# bk-circ4-S.net
KiCad netlist of a schematic drawn in EAGLE
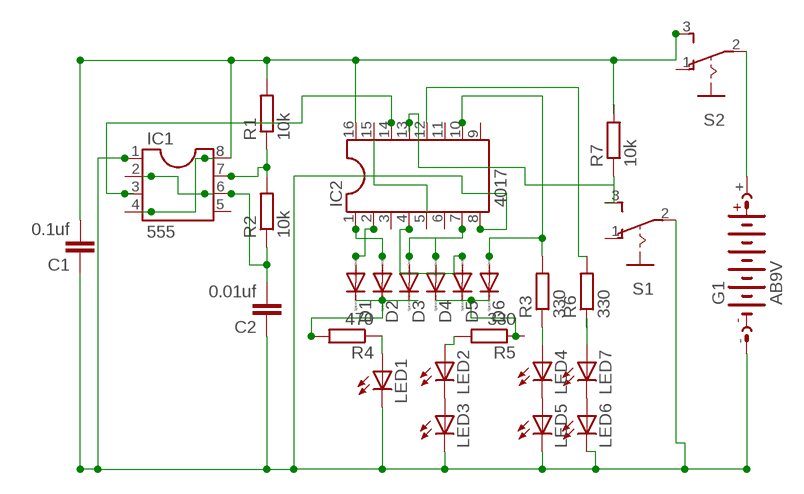
[diagram p0: schematic, sheet 1]

(export (version "E")
  (design (tool "Eeschema 10.0.6"))
  (components
    (comp (ref "C1")
      (value "0.1uf")
      (footprint "eagle-import:C025-024X044")
      (libsource (lib "eagle-import") (part "C-EU025-024X044"))
    )
    (comp (ref "C2")
      (value "0.01uf")
      (footprint "eagle-import:C025-024X044")
      (libsource (lib "eagle-import") (part "C-EU025-024X044"))
    )
    (comp (ref "D1")
      (value "1N4004")
      (footprint "eagle-import:DO41-10")
      (libsource (lib "eagle-import") (part "1N4004"))
    )
    (comp (ref "D2")
      (value "1N4004")
      (footprint "eagle-import:DO41-10")
      (libsource (lib "eagle-import") (part "1N4004"))
    )
    (comp (ref "D3")
      (value "1N4004")
      (footprint "eagle-import:DO41-10")
      (libsource (lib "eagle-import") (part "1N4004"))
    )
    (comp (ref "D4")
      (value "1N4004")
      (footprint "eagle-import:DO41-10")
      (libsource (lib "eagle-import") (part "1N4004"))
    )
    (comp (ref "D5")
      (value "1N4004")
      (footprint "eagle-import:DO41-10")
      (libsource (lib "eagle-import") (part "1N4004"))
    )
    (comp (ref "D6")
      (value "1N4004")
      (footprint "eagle-import:DO41-10")
      (libsource (lib "eagle-import") (part "1N4004"))
    )
    (comp (ref "G1")
      (value "AB9V")
      (footprint "eagle-import:AB9V")
      (libsource (lib "eagle-import") (part "AB9V"))
    )
    (comp (ref "IC1")
      (value "555")
      (footprint "eagle-import:DIL08")
      (libsource (lib "eagle-import") (part "DIL8"))
    )
    (comp (ref "IC2")
      (value "4017")
      (footprint "eagle-import:DIL16")
      (libsource (lib "eagle-import") (part "DIL16"))
    )
    (comp (ref "LED1")
      (value "LED3MM")
      (footprint "eagle-import:LED3MM")
      (libsource (lib "eagle-import") (part "LED3MM"))
    )
    (comp (ref "LED2")
      (value "LED3MM")
      (footprint "eagle-import:LED3MM")
      (libsource (lib "eagle-import") (part "LED3MM"))
    )
    (comp (ref "LED3")
      (value "LED3MM")
      (footprint "eagle-import:LED3MM")
      (libsource (lib "eagle-import") (part "LED3MM"))
    )
    (comp (ref "LED4")
      (value "LED3MM")
      (footprint "eagle-import:LED3MM")
      (libsource (lib "eagle-import") (part "LED3MM"))
    )
    (comp (ref "LED5")
      (value "LED3MM")
      (footprint "eagle-import:LED3MM")
      (libsource (lib "eagle-import") (part "LED3MM"))
    )
    (comp (ref "LED6")
      (value "LED3MM")
      (footprint "eagle-import:LED3MM")
      (libsource (lib "eagle-import") (part "LED3MM"))
    )
    (comp (ref "LED7")
      (value "LED3MM")
      (footprint "eagle-import:LED3MM")
      (libsource (lib "eagle-import") (part "LED3MM"))
    )
    (comp (ref "R1")
      (value "10k")
      (footprint "eagle-import:0207_7")
      (libsource (lib "eagle-import") (part "R-EU_0207/7"))
    )
    (comp (ref "R2")
      (value "10k")
      (footprint "eagle-import:0207_7")
      (libsource (lib "eagle-import") (part "R-EU_0207/7"))
    )
    (comp (ref "R3")
      (value "330")
      (footprint "eagle-import:0207_7")
      (libsource (lib "eagle-import") (part "R-EU_0207/7"))
    )
    (comp (ref "R4")
      (value "470")
      (footprint "eagle-import:0207_7")
      (libsource (lib "eagle-import") (part "R-EU_0207/7"))
    )
    (comp (ref "R5")
      (value "330")
      (footprint "eagle-import:0207_7")
      (libsource (lib "eagle-import") (part "R-EU_0207/7"))
    )
    (comp (ref "R6")
      (value "330")
      (footprint "eagle-import:0207_7")
      (libsource (lib "eagle-import") (part "R-EU_0207/7"))
    )
    (comp (ref "R7")
      (value "10k")
      (footprint "eagle-import:0207_7")
      (libsource (lib "eagle-import") (part "R-EU_0207/7"))
    )
    (comp (ref "S1")
      (value "255SB")
      (footprint "eagle-import:255SB")
      (libsource (lib "eagle-import") (part "255SB"))
    )
    (comp (ref "S2")
      (value "255SB")
      (footprint "eagle-import:255SB")
      (libsource (lib "eagle-import") (part "255SB"))
    )
  )
  (nets
    (net (code "1") (name "Net-(C2-Pad2)") (class "Default")
      (node (ref "C2") (pin "2") (pinfunction "2_2") (pintype "passive"))
      (node (ref "IC1") (pin "6") (pinfunction "6_6") (pintype "passive"))
      (node (ref "R2") (pin "1") (pinfunction "1_1") (pintype "passive"))
    )
    (net (code "2") (name "Net-(D1-PadC)") (class "Default")
      (node (ref "D1") (pin "C") (pinfunction "C_C") (pintype "passive"))
      (node (ref "D2") (pin "C") (pinfunction "C_C") (pintype "passive"))
      (node (ref "R4") (pin "2") (pinfunction "2_2") (pintype "passive"))
    )
    (net (code "3") (name "Net-(D4-PadC)") (class "Default")
      (node (ref "D4") (pin "C") (pinfunction "C_C") (pintype "passive"))
      (node (ref "D6") (pin "C") (pinfunction "C_C") (pintype "passive"))
    )
    (net (code "4") (name "Net-(IC1-Pad3)") (class "Default")
      (node (ref "IC1") (pin "3") (pinfunction "3_3") (pintype "passive"))
      (node (ref "IC2") (pin "14") (pinfunction "14_14") (pintype "passive"))
    )
    (net (code "5") (name "Net-(IC1-Pad7)") (class "Default")
      (node (ref "IC1") (pin "7") (pinfunction "7_7") (pintype "passive"))
      (node (ref "R1") (pin "1") (pinfunction "1_1") (pintype "passive"))
      (node (ref "R2") (pin "2") (pinfunction "2_2") (pintype "passive"))
    )
    (net (code "6") (name "Net-(IC2-Pad10)") (class "Default")
      (node (ref "IC2") (pin "10") (pinfunction "10_10") (pintype "passive"))
      (node (ref "R3") (pin "2") (pinfunction "2_2") (pintype "passive"))
    )
    (net (code "7") (name "Net-(IC2-Pad12)") (class "Default")
      (node (ref "IC2") (pin "12") (pinfunction "12_12") (pintype "passive"))
      (node (ref "R6") (pin "2") (pinfunction "2_2") (pintype "passive"))
    )
    (net (code "8") (name "Net-(LED1-C)") (class "Default")
      (node (ref "C1") (pin "1") (pinfunction "1_1") (pintype "passive"))
      (node (ref "C2") (pin "1") (pinfunction "1_1") (pintype "passive"))
      (node (ref "G1") (pin "-") (pinfunction "-_-") (pintype "passive"))
      (node (ref "IC1") (pin "1") (pinfunction "1_1") (pintype "passive"))
      (node (ref "IC2") (pin "8") (pinfunction "8_8") (pintype "passive"))
      (node (ref "LED1") (pin "K") (pinfunction "C_K") (pintype "passive"))
      (node (ref "LED3") (pin "K") (pinfunction "C_K") (pintype "passive"))
      (node (ref "LED5") (pin "K") (pinfunction "C_K") (pintype "passive"))
      (node (ref "LED6") (pin "K") (pinfunction "C_K") (pintype "passive"))
      (node (ref "S1") (pin "2") (pinfunction "P_2") (pintype "passive"))
    )
    (net (code "9") (name "Net-(LED1-PadA)") (class "Default")
      (node (ref "LED1") (pin "A") (pinfunction "A_A") (pintype "passive"))
      (node (ref "R4") (pin "1") (pinfunction "1_1") (pintype "passive"))
    )
    (net (code "10") (name "Net-(LED2-C)") (class "Default")
      (node (ref "LED2") (pin "K") (pinfunction "C_K") (pintype "passive"))
      (node (ref "LED3") (pin "A") (pinfunction "A_A") (pintype "passive"))
    )
    (net (code "11") (name "Net-(LED2-PadA)") (class "Default")
      (node (ref "LED2") (pin "A") (pinfunction "A_A") (pintype "passive"))
      (node (ref "R5") (pin "2") (pinfunction "2_2") (pintype "passive"))
    )
    (net (code "12") (name "Net-(LED4-C)") (class "Default")
      (node (ref "LED4") (pin "K") (pinfunction "C_K") (pintype "passive"))
      (node (ref "LED5") (pin "A") (pinfunction "A_A") (pintype "passive"))
    )
    (net (code "13") (name "Net-(LED4-PadA)") (class "Default")
      (node (ref "LED4") (pin "A") (pinfunction "A_A") (pintype "passive"))
      (node (ref "R3") (pin "1") (pinfunction "1_1") (pintype "passive"))
    )
    (net (code "14") (name "Net-(LED7-C)") (class "Default")
      (node (ref "LED6") (pin "A") (pinfunction "A_A") (pintype "passive"))
      (node (ref "LED7") (pin "K") (pinfunction "C_K") (pintype "passive"))
    )
    (net (code "15") (name "Net-(S1-S)") (class "Default")
      (node (ref "IC2") (pin "13") (pinfunction "13_13") (pintype "passive"))
      (node (ref "R7") (pin "1") (pinfunction "1_1") (pintype "passive"))
      (node (ref "S1") (pin "3") (pinfunction "S_3") (pintype "passive"))
    )
    (net (code "16") (name "Net-(S2-P)") (class "Default")
      (node (ref "G1") (pin "+") (pinfunction "+_+") (pintype "passive"))
      (node (ref "S2") (pin "2") (pinfunction "P_2") (pintype "passive"))
    )
    (net (code "17") (name "Net-(S2-S)") (class "Default")
      (node (ref "C1") (pin "2") (pinfunction "2_2") (pintype "passive"))
      (node (ref "IC1") (pin "8") (pinfunction "8_8") (pintype "passive"))
      (node (ref "IC2") (pin "16") (pinfunction "16_16") (pintype "passive"))
      (node (ref "R1") (pin "2") (pinfunction "2_2") (pintype "passive"))
      (node (ref "S2") (pin "3") (pinfunction "S_3") (pintype "passive"))
    )
    (net (code "18") (name "unconnected-(D1-PadA)") (class "Default")
      (node (ref "D1") (pin "A") (pinfunction "A_A") (pintype "passive"))
    )
    (net (code "19") (name "unconnected-(D2-PadA)") (class "Default")
      (node (ref "D2") (pin "A") (pinfunction "A_A") (pintype "passive"))
    )
    (net (code "20") (name "unconnected-(D3-PadA)") (class "Default")
      (node (ref "D3") (pin "A") (pinfunction "A_A") (pintype "passive"))
    )
    (net (code "21") (name "unconnected-(D3-PadC)") (class "Default")
      (node (ref "D3") (pin "C") (pinfunction "C_C") (pintype "passive"))
    )
    (net (code "22") (name "unconnected-(D4-PadA)") (class "Default")
      (node (ref "D4") (pin "A") (pinfunction "A_A") (pintype "passive"))
    )
    (net (code "23") (name "unconnected-(D5-PadA)") (class "Default")
      (node (ref "D5") (pin "A") (pinfunction "A_A") (pintype "passive"))
    )
    (net (code "24") (name "unconnected-(D5-PadC)") (class "Default")
      (node (ref "D5") (pin "C") (pinfunction "C_C") (pintype "passive"))
    )
    (net (code "25") (name "unconnected-(D6-PadA)") (class "Default")
      (node (ref "D6") (pin "A") (pinfunction "A_A") (pintype "passive"))
    )
    (net (code "26") (name "unconnected-(IC1-Pad2)") (class "Default")
      (node (ref "IC1") (pin "2") (pinfunction "2_2") (pintype "passive"))
    )
    (net (code "27") (name "unconnected-(IC1-Pad4)") (class "Default")
      (node (ref "IC1") (pin "4") (pinfunction "4_4") (pintype "passive"))
    )
    (net (code "28") (name "unconnected-(IC1-Pad5)") (class "Default")
      (node (ref "IC1") (pin "5") (pinfunction "5_5") (pintype "passive"))
    )
    (net (code "29") (name "unconnected-(IC2-Pad1)") (class "Default")
      (node (ref "IC2") (pin "1") (pinfunction "1_1") (pintype "passive"))
    )
    (net (code "30") (name "unconnected-(IC2-Pad2)") (class "Default")
      (node (ref "IC2") (pin "2") (pinfunction "2_2") (pintype "passive"))
    )
    (net (code "31") (name "unconnected-(IC2-Pad3)") (class "Default")
      (node (ref "IC2") (pin "3") (pinfunction "3_3") (pintype "passive"))
    )
    (net (code "32") (name "unconnected-(IC2-Pad4)") (class "Default")
      (node (ref "IC2") (pin "4") (pinfunction "4_4") (pintype "passive"))
    )
    (net (code "33") (name "unconnected-(IC2-Pad5)") (class "Default")
      (node (ref "IC2") (pin "5") (pinfunction "5_5") (pintype "passive"))
    )
    (net (code "34") (name "unconnected-(IC2-Pad6)") (class "Default")
      (node (ref "IC2") (pin "6") (pinfunction "6_6") (pintype "passive"))
    )
    (net (code "35") (name "unconnected-(IC2-Pad7)") (class "Default")
      (node (ref "IC2") (pin "7") (pinfunction "7_7") (pintype "passive"))
    )
    (net (code "36") (name "unconnected-(IC2-Pad9)") (class "Default")
      (node (ref "IC2") (pin "9") (pinfunction "9_9") (pintype "passive"))
    )
    (net (code "37") (name "unconnected-(IC2-Pad11)") (class "Default")
      (node (ref "IC2") (pin "11") (pinfunction "11_11") (pintype "passive"))
    )
    (net (code "38") (name "unconnected-(IC2-Pad15)") (class "Default")
      (node (ref "IC2") (pin "15") (pinfunction "15_15") (pintype "passive"))
    )
    (net (code "39") (name "unconnected-(LED7-PadA)") (class "Default")
      (node (ref "LED7") (pin "A") (pinfunction "A_A") (pintype "passive"))
    )
    (net (code "40") (name "unconnected-(R5-Pad1)") (class "Default")
      (node (ref "R5") (pin "1") (pinfunction "1_1") (pintype "passive"))
    )
    (net (code "41") (name "unconnected-(R6-Pad1)") (class "Default")
      (node (ref "R6") (pin "1") (pinfunction "1_1") (pintype "passive"))
    )
    (net (code "42") (name "unconnected-(R7-Pad2)") (class "Default")
      (node (ref "R7") (pin "2") (pinfunction "2_2") (pintype "passive"))
    )
    (net (code "43") (name "unconnected-(S1-O-Pad1)") (class "Default")
      (node (ref "S1") (pin "1") (pinfunction "O_1") (pintype "passive"))
    )
    (net (code "44") (name "unconnected-(S2-O-Pad1)") (class "Default")
      (node (ref "S2") (pin "1") (pinfunction "O_1") (pintype "passive"))
    )
  )
)
